# Power3.net
KiCad netlist of a schematic drawn in Altium Designer
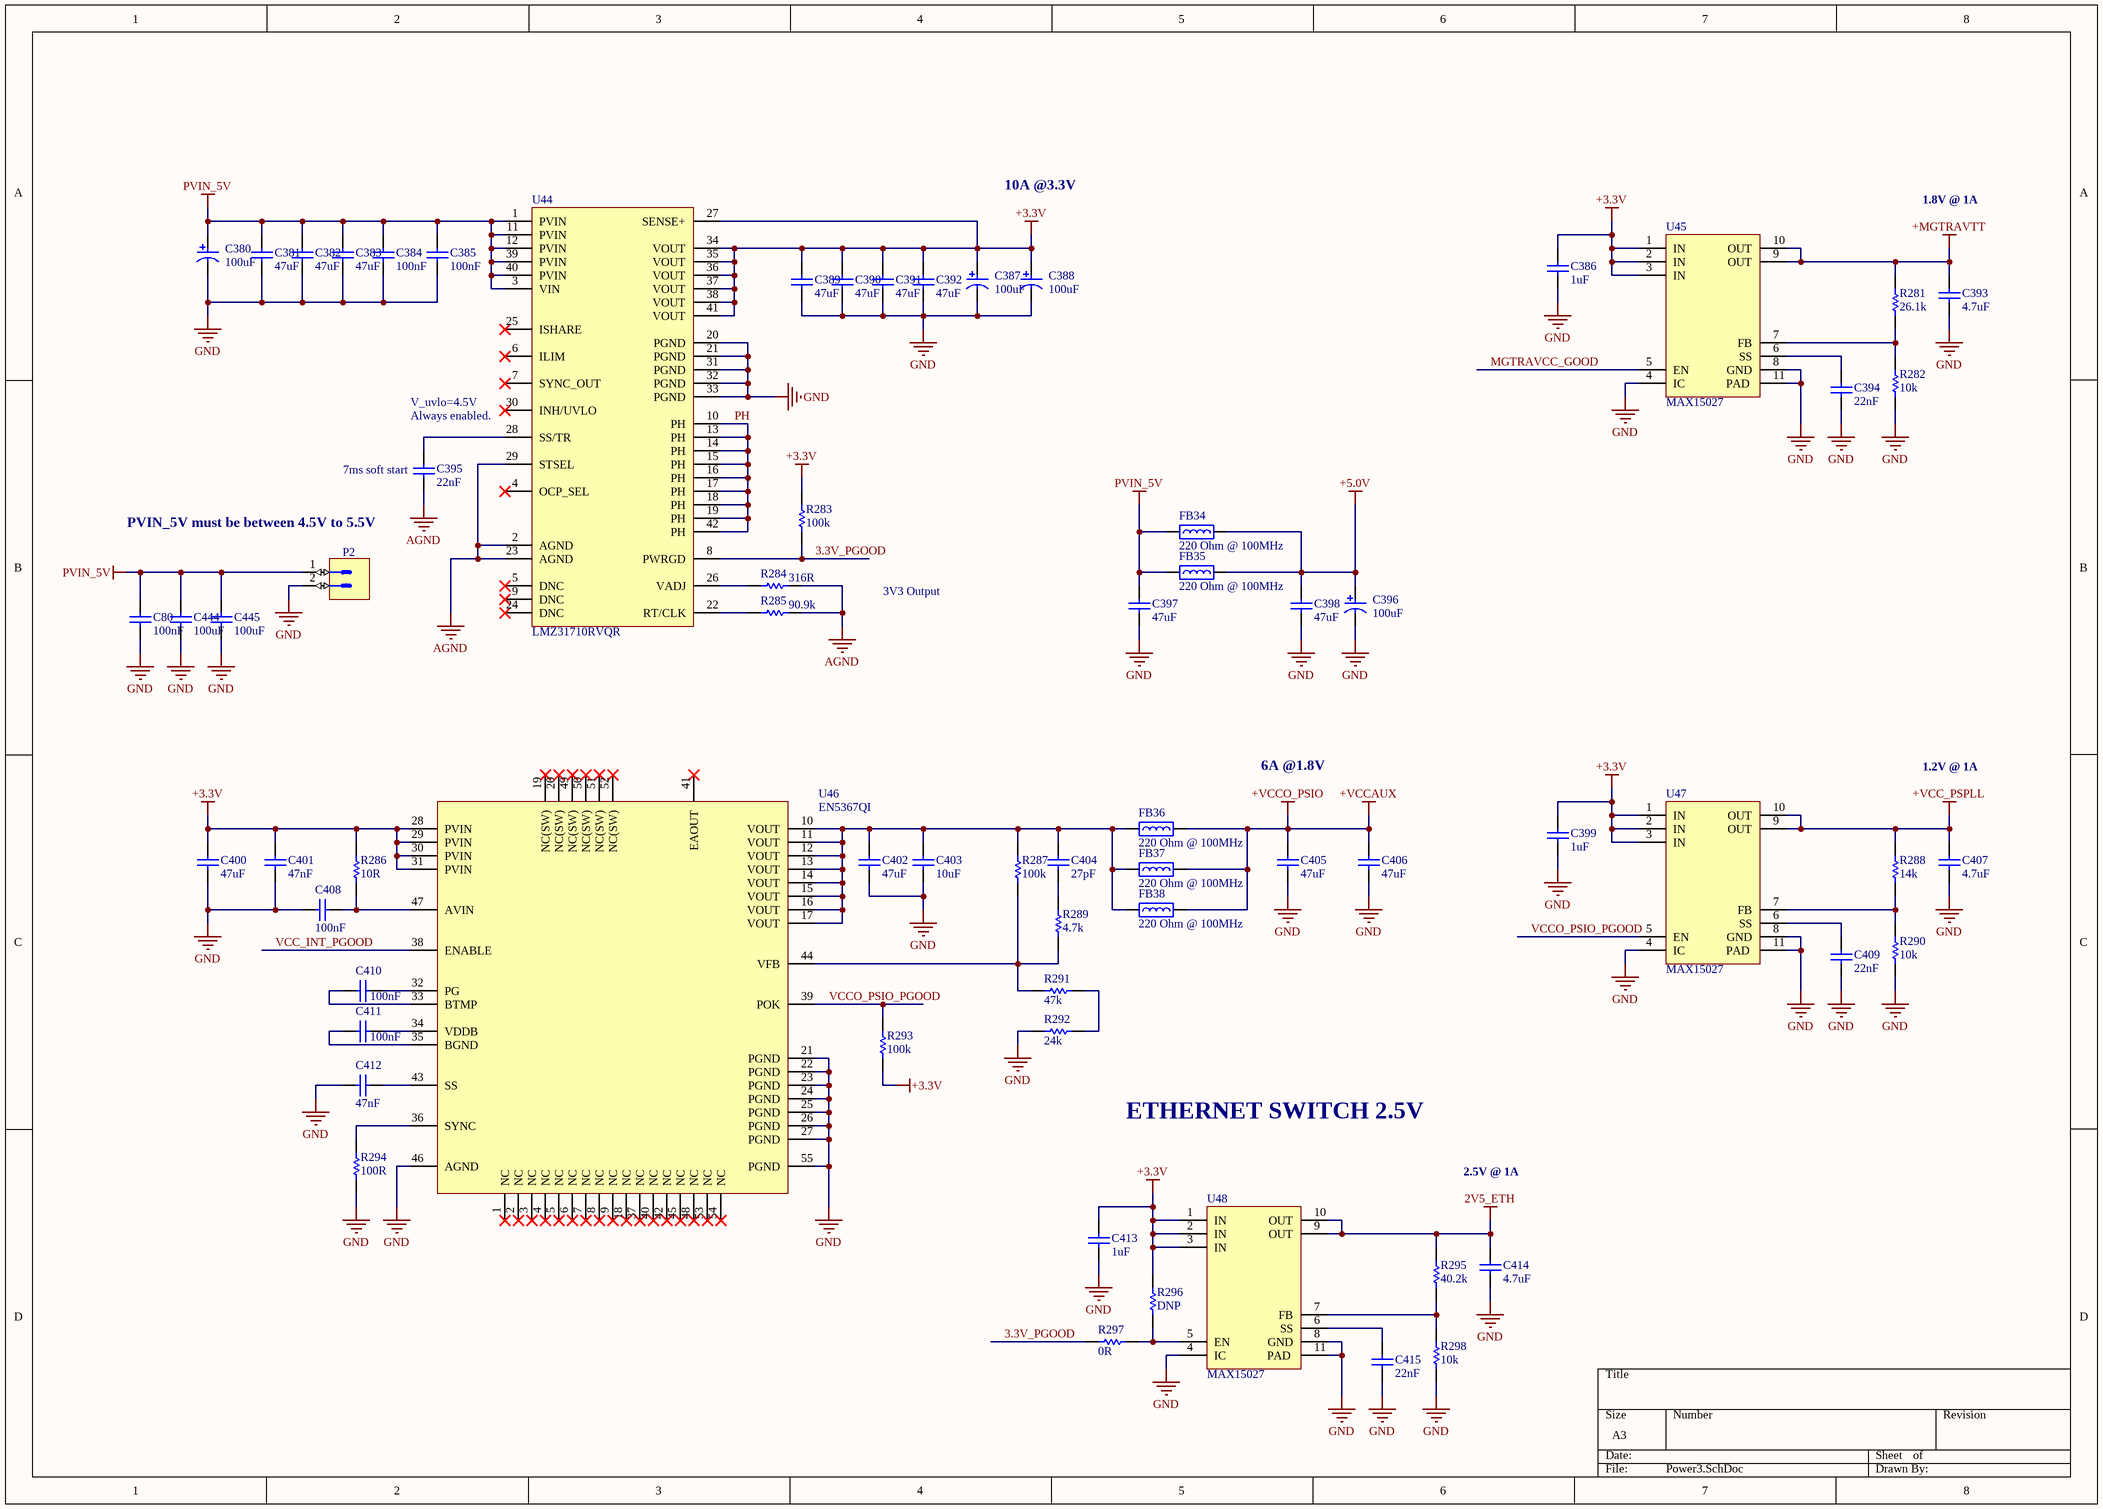
[diagram p0: Power3.SchDoc]

(export (version "E")
  (design (tool "Eeschema 10.0.6"))
  (components
    (comp (ref "C80")
      (value "100nF")
      (footprint "CAPC1005L_0402")
      (description "CAP CER 0.1UF 25V X7R 0402")
      (fields (field (name "VOLTAGE") "25V") (field (name "TOLERANCE") "10%"))
      (libsource (lib "Ultrascale_SchLib") (part "CAPCER0402X7R100N25V_10T"))
    )
    (comp (ref "C380")
      (value "100uF")
      (footprint "AVX_TAN_F95_P_0905")
      (description "CAP TANT 100UF 6.3V 20% 0805")
      (fields (field (name "VOLTAGE") "6.3V") (field (name "TOLERANCE") "20%"))
      (libsource (lib "Ultrascale_SchLib") (part "CAPELE0905TAN100U6V3_20T"))
    )
    (comp (ref "C381")
      (value "47uF")
      (footprint "CAPC3216L_1206")
      (description "CAP CER 47UF 25V X5R 1206")
      (fields (field (name "VOLTAGE") "25V") (field (name "TOLERANCE") "20%"))
      (libsource (lib "Ultrascale_SchLib") (part "CAPCER1206X5R47U25V_20T"))
    )
    (comp (ref "C382")
      (value "47uF")
      (footprint "CAPC3216L_1206")
      (description "CAP CER 47UF 25V X5R 1206")
      (fields (field (name "VOLTAGE") "25V") (field (name "TOLERANCE") "20%"))
      (libsource (lib "Ultrascale_SchLib") (part "CAPCER1206X5R47U25V_20T"))
    )
    (comp (ref "C383")
      (value "47uF")
      (footprint "CAPC3216L_1206")
      (description "CAP CER 47UF 25V X5R 1206")
      (fields (field (name "VOLTAGE") "25V") (field (name "TOLERANCE") "20%"))
      (libsource (lib "Ultrascale_SchLib") (part "CAPCER1206X5R47U25V_20T"))
    )
    (comp (ref "C384")
      (value "100nF")
      (footprint "CAPC1005L_0402")
      (description "CAP CER 0.1UF 25V X7R 0402")
      (fields (field (name "VOLTAGE") "25V") (field (name "TOLERANCE") "10%"))
      (libsource (lib "Ultrascale_SchLib") (part "CAPCER0402X7R100N25V_10T"))
    )
    (comp (ref "C385")
      (value "100nF")
      (footprint "CAPC1005L_0402")
      (description "CAP CER 0.1UF 25V X7R 0402")
      (fields (field (name "VOLTAGE") "25V") (field (name "TOLERANCE") "10%"))
      (libsource (lib "Ultrascale_SchLib") (part "CAPCER0402X7R100N25V_10T"))
    )
    (comp (ref "C386")
      (value "1uF")
      (footprint "CAPC1005L_0402")
      (description "CAP CER 1UF 16V X5R 0402")
      (fields (field (name "VOLTAGE") "16V") (field (name "TOLERANCE") "20%"))
      (libsource (lib "Ultrascale_SchLib") (part "CAPCER0402X5R1U16V_20T"))
    )
    (comp (ref "C387")
      (value "100uF")
      (footprint "AVX_TAN_F95_P_0905")
      (description "CAP TANT 100UF 6.3V 20% 0805")
      (fields (field (name "VOLTAGE") "6.3V") (field (name "TOLERANCE") "20%"))
      (libsource (lib "Ultrascale_SchLib") (part "CAPELE0905TAN100U6V3_20T"))
    )
    (comp (ref "C388")
      (value "100uF")
      (footprint "AVX_TAN_F95_P_0905")
      (description "CAP TANT 100UF 6.3V 20% 0805")
      (fields (field (name "VOLTAGE") "6.3V") (field (name "TOLERANCE") "20%"))
      (libsource (lib "Ultrascale_SchLib") (part "CAPELE0905TAN100U6V3_20T"))
    )
    (comp (ref "C389")
      (value "47uF")
      (footprint "CAPC3216L_1206")
      (description "CAP CER 47UF 25V X5R 1206")
      (fields (field (name "VOLTAGE") "25V") (field (name "TOLERANCE") "20%"))
      (libsource (lib "Ultrascale_SchLib") (part "CAPCER1206X5R47U25V_20T"))
    )
    (comp (ref "C390")
      (value "47uF")
      (footprint "CAPC3216L_1206")
      (description "CAP CER 47UF 25V X5R 1206")
      (fields (field (name "VOLTAGE") "25V") (field (name "TOLERANCE") "20%"))
      (libsource (lib "Ultrascale_SchLib") (part "CAPCER1206X5R47U25V_20T"))
    )
    (comp (ref "C391")
      (value "47uF")
      (footprint "CAPC3216L_1206")
      (description "CAP CER 47UF 25V X5R 1206")
      (fields (field (name "VOLTAGE") "25V") (field (name "TOLERANCE") "20%"))
      (libsource (lib "Ultrascale_SchLib") (part "CAPCER1206X5R47U25V_20T"))
    )
    (comp (ref "C392")
      (value "47uF")
      (footprint "CAPC3216L_1206")
      (description "CAP CER 47UF 25V X5R 1206")
      (fields (field (name "VOLTAGE") "25V") (field (name "TOLERANCE") "20%"))
      (libsource (lib "Ultrascale_SchLib") (part "CAPCER1206X5R47U25V_20T"))
    )
    (comp (ref "C393")
      (value "4.7uF")
      (footprint "CAPC1005L_0402")
      (description "CAP CER 4.7UF 10V X5R 0402")
      (fields (field (name "VOLTAGE") "10V") (field (name "TOLERANCE") "10%"))
      (libsource (lib "Ultrascale_SchLib") (part "CAPCER0402X5R4U710V_10T"))
    )
    (comp (ref "C394")
      (value "22nF")
      (footprint "CAPC1005L_0402")
      (description "CAP CER 0.022UF 50V X7R 0402")
      (fields (field (name "VOLTAGE") "50V") (field (name "TOLERANCE") "10%"))
      (libsource (lib "Ultrascale_SchLib") (part "CAPCER0402X7R22N50V_10T"))
    )
    (comp (ref "C395")
      (value "22nF")
      (footprint "CAPC1005L_0402")
      (description "CAP CER 0.022UF 50V X7R 0402")
      (fields (field (name "VOLTAGE") "50V") (field (name "TOLERANCE") "10%"))
      (libsource (lib "Ultrascale_SchLib") (part "CAPCER0402X7R22N50V_10T"))
    )
    (comp (ref "C396")
      (value "100uF")
      (footprint "AVX_TAN_F95_P_0905")
      (description "CAP TANT 100UF 6.3V 20% 0805")
      (fields (field (name "VOLTAGE") "6.3V") (field (name "TOLERANCE") "20%"))
      (libsource (lib "Ultrascale_SchLib") (part "CAPELE0905TAN100U6V3_20T"))
    )
    (comp (ref "C397")
      (value "47uF")
      (footprint "CAPC3216L_1206")
      (description "CAP CER 47UF 25V X5R 1206")
      (fields (field (name "VOLTAGE") "25V") (field (name "TOLERANCE") "20%"))
      (libsource (lib "Ultrascale_SchLib") (part "CAPCER1206X5R47U25V_20T"))
    )
    (comp (ref "C398")
      (value "47uF")
      (footprint "CAPC3216L_1206")
      (description "CAP CER 47UF 25V X5R 1206")
      (fields (field (name "VOLTAGE") "25V") (field (name "TOLERANCE") "20%"))
      (libsource (lib "Ultrascale_SchLib") (part "CAPCER1206X5R47U25V_20T"))
    )
    (comp (ref "C399")
      (value "1uF")
      (footprint "CAPC1005L_0402")
      (description "CAP CER 1UF 16V X5R 0402")
      (fields (field (name "VOLTAGE") "16V") (field (name "TOLERANCE") "20%"))
      (libsource (lib "Ultrascale_SchLib") (part "CAPCER0402X5R1U16V_20T"))
    )
    (comp (ref "C400")
      (value "47uF")
      (footprint "CAPC3216L_1206")
      (description "CAP CER 47UF 25V X5R 1206")
      (fields (field (name "VOLTAGE") "25V") (field (name "TOLERANCE") "20%"))
      (libsource (lib "Ultrascale_SchLib") (part "CAPCER1206X5R47U25V_20T"))
    )
    (comp (ref "C401")
      (value "47nF")
      (footprint "CAPC2012L_0805")
      (description "CAP CER 0.047UF 50V X7R 0805")
      (fields (field (name "VOLTAGE") "50V") (field (name "TOLERANCE") "10%"))
      (libsource (lib "Ultrascale_SchLib") (part "CAPCER0805X5R47N50V_10T"))
    )
    (comp (ref "C402")
      (value "47uF")
      (footprint "CAPC3216L_1206")
      (description "CAP CER 47UF 25V X5R 1206")
      (fields (field (name "VOLTAGE") "25V") (field (name "TOLERANCE") "20%"))
      (libsource (lib "Ultrascale_SchLib") (part "CAPCER1206X5R47U25V_20T"))
    )
    (comp (ref "C403")
      (value "10uF")
      (footprint "CAPC1005L_0402")
      (description "CAP CER 10UF 10V X5R 0402")
      (fields (field (name "VOLTAGE") "10V") (field (name "TOLERANCE") "20%"))
      (libsource (lib "Ultrascale_SchLib") (part "CAPCER0402X5R10U10V_20T"))
    )
    (comp (ref "C404")
      (value "27pF")
      (footprint "CAPC1005L_0402")
      (description "CAP CER 27PF 50V C0G/NP0 0402")
      (fields (field (name "VOLTAGE") "50V") (field (name "TOLERANCE") "5%"))
      (libsource (lib "Ultrascale_SchLib") (part "CAPCER0402C0G27P50V_5T"))
    )
    (comp (ref "C405")
      (value "47uF")
      (footprint "CAPC3216L_1206")
      (description "CAP CER 47UF 25V X5R 1206")
      (fields (field (name "VOLTAGE") "25V") (field (name "TOLERANCE") "20%"))
      (libsource (lib "Ultrascale_SchLib") (part "CAPCER1206X5R47U25V_20T"))
    )
    (comp (ref "C406")
      (value "47uF")
      (footprint "CAPC3216L_1206")
      (description "CAP CER 47UF 25V X5R 1206")
      (fields (field (name "VOLTAGE") "25V") (field (name "TOLERANCE") "20%"))
      (libsource (lib "Ultrascale_SchLib") (part "CAPCER1206X5R47U25V_20T"))
    )
    (comp (ref "C407")
      (value "4.7uF")
      (footprint "CAPC1005L_0402")
      (description "CAP CER 4.7UF 10V X5R 0402")
      (fields (field (name "VOLTAGE") "10V") (field (name "TOLERANCE") "10%"))
      (libsource (lib "Ultrascale_SchLib") (part "CAPCER0402X5R4U710V_10T"))
    )
    (comp (ref "C408")
      (value "100nF")
      (footprint "CAPC1005L_0402")
      (description "CAP CER 0.1UF 25V X7R 0402")
      (fields (field (name "VOLTAGE") "25V") (field (name "TOLERANCE") "10%"))
      (libsource (lib "Ultrascale_SchLib") (part "CAPCER0402X7R100N25V_10T"))
    )
    (comp (ref "C409")
      (value "22nF")
      (footprint "CAPC1005L_0402")
      (description "CAP CER 0.022UF 50V X7R 0402")
      (fields (field (name "VOLTAGE") "50V") (field (name "TOLERANCE") "10%"))
      (libsource (lib "Ultrascale_SchLib") (part "CAPCER0402X7R22N50V_10T"))
    )
    (comp (ref "C410")
      (value "100nF")
      (footprint "CAPC1005L_0402")
      (description "CAP CER 0.1UF 25V X7R 0402")
      (fields (field (name "VOLTAGE") "25V") (field (name "TOLERANCE") "10%"))
      (libsource (lib "Ultrascale_SchLib") (part "CAPCER0402X7R100N25V_10T"))
    )
    (comp (ref "C411")
      (value "100nF")
      (footprint "CAPC1005L_0402")
      (description "CAP CER 0.1UF 25V X7R 0402")
      (fields (field (name "VOLTAGE") "25V") (field (name "TOLERANCE") "10%"))
      (libsource (lib "Ultrascale_SchLib") (part "CAPCER0402X7R100N25V_10T"))
    )
    (comp (ref "C412")
      (value "47nF")
      (footprint "CAPC2012L_0805")
      (description "CAP CER 0.047UF 50V X7R 0805")
      (fields (field (name "VOLTAGE") "50V") (field (name "TOLERANCE") "10%"))
      (libsource (lib "Ultrascale_SchLib") (part "CAPCER0805X5R47N50V_10T"))
    )
    (comp (ref "C413")
      (value "1uF")
      (footprint "CAPC1005L_0402")
      (description "CAP CER 1UF 16V X5R 0402")
      (fields (field (name "VOLTAGE") "16V") (field (name "TOLERANCE") "20%"))
      (libsource (lib "Ultrascale_SchLib") (part "CAPCER0402X5R1U16V_20T"))
    )
    (comp (ref "C414")
      (value "4.7uF")
      (footprint "CAPC1005L_0402")
      (description "CAP CER 4.7UF 10V X5R 0402")
      (fields (field (name "VOLTAGE") "10V") (field (name "TOLERANCE") "10%"))
      (libsource (lib "Ultrascale_SchLib") (part "CAPCER0402X5R4U710V_10T"))
    )
    (comp (ref "C415")
      (value "22nF")
      (footprint "CAPC1005L_0402")
      (description "CAP CER 0.022UF 50V X7R 0402")
      (fields (field (name "VOLTAGE") "50V") (field (name "TOLERANCE") "10%"))
      (libsource (lib "Ultrascale_SchLib") (part "CAPCER0402X7R22N50V_10T"))
    )
    (comp (ref "C444")
      (value "100uF")
      (footprint "CAPC3225N_1210")
      (description "CAP CER 100UF 16V X5R 1210")
      (fields (field (name "VOLTAGE") "16V") (field (name "TOLERANCE") "20%"))
      (libsource (lib "Ultrascale_SchLib") (part "CAPCER1210X5R100U16V_20T"))
    )
    (comp (ref "C445")
      (value "100uF")
      (footprint "CAPC3225N_1210")
      (description "CAP CER 100UF 16V X5R 1210")
      (fields (field (name "VOLTAGE") "16V") (field (name "TOLERANCE") "20%"))
      (libsource (lib "Ultrascale_SchLib") (part "CAPCER1210X5R100U16V_20T"))
    )
    (comp (ref "FB34")
      (value "BEAD0603_220_2A5_40M")
      (footprint "INDC1608N_0603")
      (description "FERRITE BEAD 220 OHM 0603 1LN")
      (fields (field (name "IMPEDANCE @ FREQUENCY") "220 Ohm @ 100MHz"))
      (libsource (lib "Ultrascale_SchLib") (part "BEAD0603_220_2A5_40M"))
    )
    (comp (ref "FB35")
      (value "BEAD0603_220_2A5_40M")
      (footprint "INDC1608N_0603")
      (description "FERRITE BEAD 220 OHM 0603 1LN")
      (fields (field (name "IMPEDANCE @ FREQUENCY") "220 Ohm @ 100MHz"))
      (libsource (lib "Ultrascale_SchLib") (part "BEAD0603_220_2A5_40M"))
    )
    (comp (ref "FB36")
      (value "BEAD0603_220_2A5_40M")
      (footprint "INDC1608N_0603")
      (description "FERRITE BEAD 220 OHM 0603 1LN")
      (fields (field (name "IMPEDANCE @ FREQUENCY") "220 Ohm @ 100MHz"))
      (libsource (lib "Ultrascale_SchLib") (part "BEAD0603_220_2A5_40M"))
    )
    (comp (ref "FB37")
      (value "BEAD0603_220_2A5_40M")
      (footprint "INDC1608N_0603")
      (description "FERRITE BEAD 220 OHM 0603 1LN")
      (fields (field (name "IMPEDANCE @ FREQUENCY") "220 Ohm @ 100MHz"))
      (libsource (lib "Ultrascale_SchLib") (part "BEAD0603_220_2A5_40M"))
    )
    (comp (ref "FB38")
      (value "BEAD0603_220_2A5_40M")
      (footprint "INDC1608N_0603")
      (description "FERRITE BEAD 220 OHM 0603 1LN")
      (fields (field (name "IMPEDANCE @ FREQUENCY") "220 Ohm @ 100MHz"))
      (libsource (lib "Ultrascale_SchLib") (part "BEAD0603_220_2A5_40M"))
    )
    (comp (ref "P2")
      (value "KK®")
      (footprint "MOLEX_26-60-4020")
      (description "Connector 2 Male")
      (fields
        (field (name "PART NUMBER") "MOLEX_26-60-4020")
        (field (name "MANUFACTURER") "Molex, LLC")
        (field (name "AUTHOR") "CERN DEM JLC")
      )
      (libsource (lib "Ultrascale_SchLib") (part "MOLEX_26-60-4020"))
    )
    (comp (ref "R281")
      (value "26.1k")
      (footprint "RESC1005L_0402")
      (description "RES SMD 26.1K OHM 1% 1/10W 0402")
      (fields (field (name "POWER") "1/10W") (field (name "TOLERANCE") "1%"))
      (libsource (lib "Ultrascale_SchLib") (part "RES0402_26K1_0W1_1T"))
    )
    (comp (ref "R282")
      (value "10k")
      (footprint "RESC1005L_0402")
      (description "RES SMD 10K OHM 0.5% 1/16W 0402")
      (fields (field (name "POWER") "1/16W") (field (name "TOLERANCE") "0.5%"))
      (libsource (lib "Ultrascale_SchLib") (part "RES0402_10K_0W1_05T"))
    )
    (comp (ref "R283")
      (value "100k")
      (footprint "RESC1005L_0402")
      (description "RES SMD 100K OHM 1% 1/5W 0402")
      (fields (field (name "POWER") "1/5W") (field (name "TOLERANCE") "1%"))
      (libsource (lib "Ultrascale_SchLib") (part "RES0402_100K_0W2_1T"))
    )
    (comp (ref "R284")
      (value "316R")
      (footprint "RESC1005L_0402")
      (description "RES SMD 316 OHM 1% 1/16W 0402")
      (fields (field (name "POWER") "1/16W") (field (name "TOLERANCE") "1%"))
      (libsource (lib "Ultrascale_SchLib") (part "RES0402_316R_0W06_1T"))
    )
    (comp (ref "R285")
      (value "90.9k")
      (footprint "RESC1005L_0402")
      (description "RES SMD 90.9K OHM 1% 1/10W 0402")
      (fields (field (name "POWER") "1/10W") (field (name "TOLERANCE") "1%"))
      (libsource (lib "Ultrascale_SchLib") (part "RES0402_90K9_0W1_1T"))
    )
    (comp (ref "R286")
      (value "10R")
      (footprint "RESC1005L_0402")
      (description "RES SMD 10 OHM 1% 1/10W 0402")
      (fields (field (name "POWER") "1/10W") (field (name "TOLERANCE") "1%"))
      (libsource (lib "Ultrascale_SchLib") (part "RES0402_10R_0W1_1T"))
    )
    (comp (ref "R287")
      (value "100k")
      (footprint "RESC1005L_0402")
      (description "RES SMD 100K OHM 1% 1/5W 0402")
      (fields (field (name "POWER") "1/5W") (field (name "TOLERANCE") "1%"))
      (libsource (lib "Ultrascale_SchLib") (part "RES0402_100K_0W2_1T"))
    )
    (comp (ref "R288")
      (value "14k")
      (footprint "RESC1005L_0402")
      (description "RES SMD 14K OHM 1% 1/10W 0402")
      (fields (field (name "POWER") "1/10W") (field (name "TOLERANCE") "1%"))
      (libsource (lib "Ultrascale_SchLib") (part "RES0402_14K_0W1_1T"))
    )
    (comp (ref "R289")
      (value "4.7k")
      (footprint "RESC1005L_0402")
      (description "RES SMD 4.7K OHM 1% 1/10W 0402")
      (fields (field (name "POWER") "1/10W") (field (name "TOLERANCE") "1%"))
      (libsource (lib "Ultrascale_SchLib") (part "RES0402_4K7_0W1_1T"))
    )
    (comp (ref "R290")
      (value "10k")
      (footprint "RESC1005L_0402")
      (description "RES SMD 10K OHM 0.5% 1/16W 0402")
      (fields (field (name "POWER") "1/16W") (field (name "TOLERANCE") "0.5%"))
      (libsource (lib "Ultrascale_SchLib") (part "RES0402_10K_0W1_05T"))
    )
    (comp (ref "R291")
      (value "47k")
      (footprint "RESC1005L_0402")
      (description "RES SMD 47K OHM 1% 1/10W 0402")
      (fields (field (name "POWER") "1/10W") (field (name "TOLERANCE") "1%"))
      (libsource (lib "Ultrascale_SchLib") (part "RES0402_47K_0W1"))
    )
    (comp (ref "R292")
      (value "24k")
      (footprint "RESC1005L_0402")
      (description "RES SMD 24K OHM 1% 1/10W 0402")
      (fields (field (name "POWER") "1/10W") (field (name "TOLERANCE") "1%"))
      (libsource (lib "Ultrascale_SchLib") (part "RES0402_24K_0W1"))
    )
    (comp (ref "R293")
      (value "100k")
      (footprint "RESC1005L_0402")
      (description "RES SMD 100K OHM 1% 1/5W 0402")
      (fields (field (name "POWER") "1/5W") (field (name "TOLERANCE") "1%"))
      (libsource (lib "Ultrascale_SchLib") (part "RES0402_100K_0W2_1T"))
    )
    (comp (ref "R294")
      (value "100R")
      (footprint "RESC1005L_0402")
      (description "RES SMD 100 OHM 1% 1/10W 0402")
      (fields (field (name "POWER") "1/10W") (field (name "TOLERANCE") "1%"))
      (libsource (lib "Ultrascale_SchLib") (part "RES0402_100R_0W1_1T"))
    )
    (comp (ref "R295")
      (value "40.2k")
      (footprint "RESC1005L_0402")
      (description "RES SMD 40.2K OHM 1% 1/10W 0402")
      (fields (field (name "POWER") "1/10W") (field (name "TOLERANCE") "1%"))
      (libsource (lib "Ultrascale_SchLib") (part "RES0402_40K2_0W1_1T"))
    )
    (comp (ref "R296")
      (value "DNP")
      (footprint "RESC1005L_0402")
      (description "RES SMD 0402 Footprint")
      (fields (field (name "Comment") "RES0402"))
      (libsource (lib "Ultrascale_SchLib") (part "RES0402"))
    )
    (comp (ref "R297")
      (value "0R")
      (footprint "RESC1005L_0402")
      (description "RES SMD 0 OHM JUMPER 1/16W 0402")
      (fields (field (name "POWER") "0.063W, 1/16W") (field (name "Comment") "RES0402_0R"))
      (libsource (lib "Ultrascale_SchLib") (part "RES0402_0R"))
    )
    (comp (ref "R298")
      (value "10k")
      (footprint "RESC1005L_0402")
      (description "RES SMD 10K OHM 0.5% 1/16W 0402")
      (fields (field (name "POWER") "1/16W") (field (name "TOLERANCE") "0.5%"))
      (libsource (lib "Ultrascale_SchLib") (part "RES0402_10K_0W1_05T"))
    )
    (comp (ref "U44")
      (value "LMZ31710RVQR")
      (footprint "LMZ31710RVQR")
      (description "DC/DC CONVERTER 0.6-5.5V 55W")
      (libsource (lib "Ultrascale_SchLib") (part "LMZ31710RVQR"))
    )
    (comp (ref "U45")
      (value "MAX15027")
      (footprint "MAX15027_T1033+1_V")
      (description "IC REG LINEAR POS ADJ 1A 10TDFN")
      (libsource (lib "Ultrascale_SchLib") (part "MAX15027"))
    )
    (comp (ref "U46")
      (value "EN5367QI")
      (footprint "QFN54-EN5367QI")
      (description "DC/DC CONVERTER 0.6-4.9V 29W")
      (libsource (lib "Ultrascale_SchLib") (part "EN5367QI"))
    )
    (comp (ref "U47")
      (value "MAX15027")
      (footprint "MAX15027_T1033+1_V")
      (description "IC REG LINEAR POS ADJ 1A 10TDFN")
      (libsource (lib "Ultrascale_SchLib") (part "MAX15027"))
    )
    (comp (ref "U48")
      (value "MAX15027")
      (footprint "MAX15027_T1033+1_V")
      (description "IC REG LINEAR POS ADJ 1A 10TDFN")
      (libsource (lib "Ultrascale_SchLib") (part "MAX15027"))
    )
  )
  (nets
    (net (code "1") (name "+3.3V") (class "Default")
      (node (ref "C386") (pin "2") (pinfunction "2_2") (pintype "passive"))
      (node (ref "C387") (pin "1") (pinfunction "1_1") (pintype "passive"))
      (node (ref "C388") (pin "1") (pinfunction "1_1") (pintype "passive"))
      (node (ref "C389") (pin "2") (pinfunction "2_2") (pintype "passive"))
      (node (ref "C390") (pin "2") (pinfunction "2_2") (pintype "passive"))
      (node (ref "C391") (pin "2") (pinfunction "2_2") (pintype "passive"))
      (node (ref "C392") (pin "2") (pinfunction "2_2") (pintype "passive"))
      (node (ref "C399") (pin "2") (pinfunction "2_2") (pintype "passive"))
      (node (ref "C400") (pin "2") (pinfunction "2_2") (pintype "passive"))
      (node (ref "C401") (pin "2") (pinfunction "2_2") (pintype "passive"))
      (node (ref "C413") (pin "2") (pinfunction "2_2") (pintype "passive"))
      (node (ref "R283") (pin "2") (pinfunction "2_2") (pintype "passive"))
      (node (ref "R286") (pin "2") (pinfunction "2_2") (pintype "passive"))
      (node (ref "R293") (pin "2") (pinfunction "2_2") (pintype "passive"))
      (node (ref "R296") (pin "2") (pinfunction "2_2") (pintype "passive"))
      (node (ref "U44") (pin "27") (pinfunction "SENSE+_27") (pintype "power_in"))
      (node (ref "U44") (pin "34") (pinfunction "VOUT_34") (pintype "power_in"))
      (node (ref "U44") (pin "35") (pinfunction "VOUT_35") (pintype "power_in"))
      (node (ref "U44") (pin "36") (pinfunction "VOUT_36") (pintype "power_in"))
      (node (ref "U44") (pin "37") (pinfunction "VOUT_37") (pintype "power_in"))
      (node (ref "U44") (pin "38") (pinfunction "VOUT_38") (pintype "power_in"))
      (node (ref "U44") (pin "41") (pinfunction "VOUT_41") (pintype "power_in"))
      (node (ref "U45") (pin "1") (pinfunction "IN_1") (pintype "passive"))
      (node (ref "U45") (pin "2") (pinfunction "IN_2") (pintype "passive"))
      (node (ref "U45") (pin "3") (pinfunction "IN_3") (pintype "passive"))
      (node (ref "U46") (pin "28") (pinfunction "PVIN_28") (pintype "power_in"))
      (node (ref "U46") (pin "29") (pinfunction "PVIN_29") (pintype "power_in"))
      (node (ref "U46") (pin "30") (pinfunction "PVIN_30") (pintype "power_in"))
      (node (ref "U46") (pin "31") (pinfunction "PVIN_31") (pintype "power_in"))
      (node (ref "U47") (pin "1") (pinfunction "IN_1") (pintype "passive"))
      (node (ref "U47") (pin "2") (pinfunction "IN_2") (pintype "passive"))
      (node (ref "U47") (pin "3") (pinfunction "IN_3") (pintype "passive"))
      (node (ref "U48") (pin "1") (pinfunction "IN_1") (pintype "passive"))
      (node (ref "U48") (pin "2") (pinfunction "IN_2") (pintype "passive"))
      (node (ref "U48") (pin "3") (pinfunction "IN_3") (pintype "passive"))
    )
    (net (code "2") (name "+5.0V") (class "Default")
      (node (ref "C396") (pin "1") (pinfunction "1_1") (pintype "passive"))
      (node (ref "C398") (pin "2") (pinfunction "2_2") (pintype "passive"))
      (node (ref "FB34") (pin "2") (pinfunction "2_2") (pintype "passive"))
      (node (ref "FB35") (pin "2") (pinfunction "2_2") (pintype "passive"))
    )
    (net (code "3") (name "+MGTRAVTT") (class "Default")
      (node (ref "C393") (pin "2") (pinfunction "2_2") (pintype "passive"))
      (node (ref "R281") (pin "2") (pinfunction "2_2") (pintype "passive"))
      (node (ref "U45") (pin "10") (pinfunction "OUT_10") (pintype "passive"))
      (node (ref "U45") (pin "9") (pinfunction "OUT_9") (pintype "passive"))
    )
    (net (code "4") (name "+VCCAUX") (class "Default")
      (node (ref "C405") (pin "2") (pinfunction "2_2") (pintype "passive"))
      (node (ref "C406") (pin "2") (pinfunction "2_2") (pintype "passive"))
      (node (ref "FB36") (pin "2") (pinfunction "2_2") (pintype "passive"))
      (node (ref "FB37") (pin "2") (pinfunction "2_2") (pintype "passive"))
      (node (ref "FB38") (pin "2") (pinfunction "2_2") (pintype "passive"))
    )
    (net (code "5") (name "+VCC_PSPLL") (class "Default")
      (node (ref "C407") (pin "2") (pinfunction "2_2") (pintype "passive"))
      (node (ref "R288") (pin "2") (pinfunction "2_2") (pintype "passive"))
      (node (ref "U47") (pin "10") (pinfunction "OUT_10") (pintype "passive"))
      (node (ref "U47") (pin "9") (pinfunction "OUT_9") (pintype "passive"))
    )
    (net (code "6") (name "/3.3V_PGOOD") (class "Default")
      (node (ref "R283") (pin "1") (pinfunction "1_1") (pintype "passive"))
      (node (ref "R297") (pin "1") (pinfunction "1_1") (pintype "passive"))
      (node (ref "U44") (pin "8") (pinfunction "PWRGD_8") (pintype "power_in"))
    )
    (net (code "7") (name "/MGTRAVCC_GOOD") (class "Default")
      (node (ref "U45") (pin "5") (pinfunction "EN_5") (pintype "passive"))
    )
    (net (code "8") (name "/PH") (class "Default")
      (node (ref "U44") (pin "10") (pinfunction "PH_10") (pintype "power_in"))
      (node (ref "U44") (pin "13") (pinfunction "PH_13") (pintype "power_in"))
      (node (ref "U44") (pin "14") (pinfunction "PH_14") (pintype "power_in"))
      (node (ref "U44") (pin "15") (pinfunction "PH_15") (pintype "power_in"))
      (node (ref "U44") (pin "16") (pinfunction "PH_16") (pintype "power_in"))
      (node (ref "U44") (pin "17") (pinfunction "PH_17") (pintype "power_in"))
      (node (ref "U44") (pin "18") (pinfunction "PH_18") (pintype "power_in"))
      (node (ref "U44") (pin "19") (pinfunction "PH_19") (pintype "power_in"))
      (node (ref "U44") (pin "42") (pinfunction "PH_42") (pintype "power_in"))
    )
    (net (code "9") (name "/VCCO_PSIO_PGOOD") (class "Default")
      (node (ref "R293") (pin "1") (pinfunction "1_1") (pintype "passive"))
      (node (ref "U46") (pin "39") (pinfunction "POK_39") (pintype "power_in"))
      (node (ref "U47") (pin "5") (pinfunction "EN_5") (pintype "passive"))
    )
    (net (code "10") (name "/VCC_INT_PGOOD") (class "Default")
      (node (ref "U46") (pin "38") (pinfunction "ENABLE_38") (pintype "power_in"))
    )
    (net (code "11") (name "2V5_ETH") (class "Default")
      (node (ref "C414") (pin "2") (pinfunction "2_2") (pintype "passive"))
      (node (ref "R295") (pin "2") (pinfunction "2_2") (pintype "passive"))
      (node (ref "U48") (pin "10") (pinfunction "OUT_10") (pintype "passive"))
      (node (ref "U48") (pin "9") (pinfunction "OUT_9") (pintype "passive"))
    )
    (net (code "12") (name "AGND") (class "Default")
      (node (ref "C395") (pin "1") (pinfunction "1_1") (pintype "passive"))
      (node (ref "R284") (pin "2") (pinfunction "2_2") (pintype "passive"))
      (node (ref "R285") (pin "2") (pinfunction "2_2") (pintype "passive"))
      (node (ref "U44") (pin "2") (pinfunction "AGND_2") (pintype "power_in"))
      (node (ref "U44") (pin "23") (pinfunction "AGND_23") (pintype "power_in"))
      (node (ref "U44") (pin "29") (pinfunction "STSEL_29") (pintype "power_in"))
    )
    (net (code "13") (name "GND") (class "Default")
      (node (ref "C380") (pin "2") (pinfunction "2_2") (pintype "passive"))
      (node (ref "C381") (pin "1") (pinfunction "1_1") (pintype "passive"))
      (node (ref "C382") (pin "1") (pinfunction "1_1") (pintype "passive"))
      (node (ref "C383") (pin "1") (pinfunction "1_1") (pintype "passive"))
      (node (ref "C384") (pin "2") (pinfunction "2_2") (pintype "passive"))
      (node (ref "C385") (pin "2") (pinfunction "2_2") (pintype "passive"))
      (node (ref "C386") (pin "1") (pinfunction "1_1") (pintype "passive"))
      (node (ref "C387") (pin "2") (pinfunction "2_2") (pintype "passive"))
      (node (ref "C388") (pin "2") (pinfunction "2_2") (pintype "passive"))
      (node (ref "C389") (pin "1") (pinfunction "1_1") (pintype "passive"))
      (node (ref "C390") (pin "1") (pinfunction "1_1") (pintype "passive"))
      (node (ref "C391") (pin "1") (pinfunction "1_1") (pintype "passive"))
      (node (ref "C392") (pin "1") (pinfunction "1_1") (pintype "passive"))
      (node (ref "C393") (pin "1") (pinfunction "1_1") (pintype "passive"))
      (node (ref "C394") (pin "1") (pinfunction "1_1") (pintype "passive"))
      (node (ref "C396") (pin "2") (pinfunction "2_2") (pintype "passive"))
      (node (ref "C397") (pin "1") (pinfunction "1_1") (pintype "passive"))
      (node (ref "C398") (pin "1") (pinfunction "1_1") (pintype "passive"))
      (node (ref "C399") (pin "1") (pinfunction "1_1") (pintype "passive"))
      (node (ref "C400") (pin "1") (pinfunction "1_1") (pintype "passive"))
      (node (ref "C401") (pin "1") (pinfunction "1_1") (pintype "passive"))
      (node (ref "C402") (pin "1") (pinfunction "1_1") (pintype "passive"))
      (node (ref "C403") (pin "1") (pinfunction "1_1") (pintype "passive"))
      (node (ref "C405") (pin "1") (pinfunction "1_1") (pintype "passive"))
      (node (ref "C406") (pin "1") (pinfunction "1_1") (pintype "passive"))
      (node (ref "C407") (pin "1") (pinfunction "1_1") (pintype "passive"))
      (node (ref "C408") (pin "2") (pinfunction "2_2") (pintype "passive"))
      (node (ref "C409") (pin "1") (pinfunction "1_1") (pintype "passive"))
      (node (ref "C412") (pin "2") (pinfunction "2_2") (pintype "passive"))
      (node (ref "C413") (pin "1") (pinfunction "1_1") (pintype "passive"))
      (node (ref "C414") (pin "1") (pinfunction "1_1") (pintype "passive"))
      (node (ref "C415") (pin "1") (pinfunction "1_1") (pintype "passive"))
      (node (ref "C444") (pin "1") (pinfunction "1_1") (pintype "passive"))
      (node (ref "C445") (pin "1") (pinfunction "1_1") (pintype "passive"))
      (node (ref "C80") (pin "2") (pinfunction "2_2") (pintype "passive"))
      (node (ref "P2") (pin "2") (pinfunction "2_2") (pintype "bidirectional"))
      (node (ref "R282") (pin "1") (pinfunction "1_1") (pintype "passive"))
      (node (ref "R290") (pin "1") (pinfunction "1_1") (pintype "passive"))
      (node (ref "R292") (pin "1") (pinfunction "1_1") (pintype "passive"))
      (node (ref "R294") (pin "2") (pinfunction "2_2") (pintype "passive"))
      (node (ref "R298") (pin "1") (pinfunction "1_1") (pintype "passive"))
      (node (ref "U44") (pin "20") (pinfunction "PGND_20") (pintype "power_in"))
      (node (ref "U44") (pin "21") (pinfunction "PGND_21") (pintype "power_in"))
      (node (ref "U44") (pin "31") (pinfunction "PGND_31") (pintype "power_in"))
      (node (ref "U44") (pin "32") (pinfunction "PGND_32") (pintype "power_in"))
      (node (ref "U44") (pin "33") (pinfunction "PGND_33") (pintype "power_in"))
      (node (ref "U45") (pin "11") (pinfunction "PAD_11") (pintype "passive"))
      (node (ref "U45") (pin "4") (pinfunction "IC_4") (pintype "passive"))
      (node (ref "U45") (pin "8") (pinfunction "GND_8") (pintype "passive"))
      (node (ref "U46") (pin "21") (pinfunction "PGND_21") (pintype "power_in"))
      (node (ref "U46") (pin "22") (pinfunction "PGND_22") (pintype "power_in"))
      (node (ref "U46") (pin "23") (pinfunction "PGND_23") (pintype "power_in"))
      (node (ref "U46") (pin "24") (pinfunction "PGND_24") (pintype "power_in"))
      (node (ref "U46") (pin "25") (pinfunction "PGND_25") (pintype "power_in"))
      (node (ref "U46") (pin "26") (pinfunction "PGND_26") (pintype "power_in"))
      (node (ref "U46") (pin "27") (pinfunction "PGND_27") (pintype "power_in"))
      (node (ref "U46") (pin "46") (pinfunction "AGND_46") (pintype "power_in"))
      (node (ref "U46") (pin "55") (pinfunction "PGND_55") (pintype "power_in"))
      (node (ref "U47") (pin "11") (pinfunction "PAD_11") (pintype "passive"))
      (node (ref "U47") (pin "4") (pinfunction "IC_4") (pintype "passive"))
      (node (ref "U47") (pin "8") (pinfunction "GND_8") (pintype "passive"))
      (node (ref "U48") (pin "11") (pinfunction "PAD_11") (pintype "passive"))
      (node (ref "U48") (pin "4") (pinfunction "IC_4") (pintype "passive"))
      (node (ref "U48") (pin "8") (pinfunction "GND_8") (pintype "passive"))
    )
    (net (code "14") (name "Net-(C402-Pad2)") (class "Default")
      (node (ref "C402") (pin "2") (pinfunction "2_2") (pintype "passive"))
      (node (ref "C403") (pin "2") (pinfunction "2_2") (pintype "passive"))
      (node (ref "C404") (pin "2") (pinfunction "2_2") (pintype "passive"))
      (node (ref "FB36") (pin "1") (pinfunction "1_1") (pintype "passive"))
      (node (ref "FB37") (pin "1") (pinfunction "1_1") (pintype "passive"))
      (node (ref "FB38") (pin "1") (pinfunction "1_1") (pintype "passive"))
      (node (ref "R287") (pin "2") (pinfunction "2_2") (pintype "passive"))
      (node (ref "U46") (pin "10") (pinfunction "VOUT_10") (pintype "power_in"))
      (node (ref "U46") (pin "11") (pinfunction "VOUT_11") (pintype "power_in"))
      (node (ref "U46") (pin "12") (pinfunction "VOUT_12") (pintype "power_in"))
      (node (ref "U46") (pin "13") (pinfunction "VOUT_13") (pintype "power_in"))
      (node (ref "U46") (pin "14") (pinfunction "VOUT_14") (pintype "power_in"))
      (node (ref "U46") (pin "15") (pinfunction "VOUT_15") (pintype "power_in"))
      (node (ref "U46") (pin "16") (pinfunction "VOUT_16") (pintype "power_in"))
      (node (ref "U46") (pin "17") (pinfunction "VOUT_17") (pintype "power_in"))
    )
    (net (code "15") (name "Net-(C404-Pad1)") (class "Default")
      (node (ref "C404") (pin "1") (pinfunction "1_1") (pintype "passive"))
      (node (ref "R289") (pin "2") (pinfunction "2_2") (pintype "passive"))
    )
    (net (code "16") (name "Net-(R291-Pad1)") (class "Default")
      (node (ref "R291") (pin "1") (pinfunction "1_1") (pintype "passive"))
      (node (ref "R292") (pin "2") (pinfunction "2_2") (pintype "passive"))
    )
    (net (code "17") (name "Net-(U44-RT{slash}CLK)") (class "Default")
      (node (ref "R285") (pin "1") (pinfunction "1_1") (pintype "passive"))
      (node (ref "U44") (pin "22") (pinfunction "RT/CLK_22") (pintype "power_in"))
    )
    (net (code "18") (name "Net-(U44-SS{slash}TR)") (class "Default")
      (node (ref "C395") (pin "2") (pinfunction "2_2") (pintype "passive"))
      (node (ref "U44") (pin "28") (pinfunction "SS/TR_28") (pintype "power_in"))
    )
    (net (code "19") (name "Net-(U44-VADJ)") (class "Default")
      (node (ref "R284") (pin "1") (pinfunction "1_1") (pintype "passive"))
      (node (ref "U44") (pin "26") (pinfunction "VADJ_26") (pintype "power_in"))
    )
    (net (code "20") (name "Net-(U45-FB)") (class "Default")
      (node (ref "R281") (pin "1") (pinfunction "1_1") (pintype "passive"))
      (node (ref "R282") (pin "2") (pinfunction "2_2") (pintype "passive"))
      (node (ref "U45") (pin "7") (pinfunction "FB_7") (pintype "passive"))
    )
    (net (code "21") (name "Net-(U45-SS)") (class "Default")
      (node (ref "C394") (pin "2") (pinfunction "2_2") (pintype "passive"))
      (node (ref "U45") (pin "6") (pinfunction "SS_6") (pintype "passive"))
    )
    (net (code "22") (name "Net-(U46-AVIN)") (class "Default")
      (node (ref "C408") (pin "1") (pinfunction "1_1") (pintype "passive"))
      (node (ref "R286") (pin "1") (pinfunction "1_1") (pintype "passive"))
      (node (ref "U46") (pin "47") (pinfunction "AVIN_47") (pintype "power_in"))
    )
    (net (code "23") (name "Net-(U46-BGND)") (class "Default")
      (node (ref "C411") (pin "2") (pinfunction "2_2") (pintype "passive"))
      (node (ref "U46") (pin "35") (pinfunction "BGND_35") (pintype "power_in"))
    )
    (net (code "24") (name "Net-(U46-BTMP)") (class "Default")
      (node (ref "C410") (pin "2") (pinfunction "2_2") (pintype "passive"))
      (node (ref "U46") (pin "33") (pinfunction "BTMP_33") (pintype "power_in"))
    )
    (net (code "25") (name "Net-(U46-PG)") (class "Default")
      (node (ref "C410") (pin "1") (pinfunction "1_1") (pintype "passive"))
      (node (ref "U46") (pin "32") (pinfunction "PG_32") (pintype "power_in"))
    )
    (net (code "26") (name "Net-(U46-SS)") (class "Default")
      (node (ref "C412") (pin "1") (pinfunction "1_1") (pintype "passive"))
      (node (ref "U46") (pin "43") (pinfunction "SS_43") (pintype "power_in"))
    )
    (net (code "27") (name "Net-(U46-SYNC)") (class "Default")
      (node (ref "R294") (pin "1") (pinfunction "1_1") (pintype "passive"))
      (node (ref "U46") (pin "36") (pinfunction "SYNC_36") (pintype "power_in"))
    )
    (net (code "28") (name "Net-(U46-VDDB)") (class "Default")
      (node (ref "C411") (pin "1") (pinfunction "1_1") (pintype "passive"))
      (node (ref "U46") (pin "34") (pinfunction "VDDB_34") (pintype "power_in"))
    )
    (net (code "29") (name "Net-(U46-VFB)") (class "Default")
      (node (ref "R287") (pin "1") (pinfunction "1_1") (pintype "passive"))
      (node (ref "R289") (pin "1") (pinfunction "1_1") (pintype "passive"))
      (node (ref "R291") (pin "2") (pinfunction "2_2") (pintype "passive"))
      (node (ref "U46") (pin "44") (pinfunction "VFB_44") (pintype "power_in"))
    )
    (net (code "30") (name "Net-(U47-FB)") (class "Default")
      (node (ref "R288") (pin "1") (pinfunction "1_1") (pintype "passive"))
      (node (ref "R290") (pin "2") (pinfunction "2_2") (pintype "passive"))
      (node (ref "U47") (pin "7") (pinfunction "FB_7") (pintype "passive"))
    )
    (net (code "31") (name "Net-(U47-SS)") (class "Default")
      (node (ref "C409") (pin "2") (pinfunction "2_2") (pintype "passive"))
      (node (ref "U47") (pin "6") (pinfunction "SS_6") (pintype "passive"))
    )
    (net (code "32") (name "Net-(U48-EN)") (class "Default")
      (node (ref "R296") (pin "1") (pinfunction "1_1") (pintype "passive"))
      (node (ref "R297") (pin "2") (pinfunction "2_2") (pintype "passive"))
      (node (ref "U48") (pin "5") (pinfunction "EN_5") (pintype "passive"))
    )
    (net (code "33") (name "Net-(U48-FB)") (class "Default")
      (node (ref "R295") (pin "1") (pinfunction "1_1") (pintype "passive"))
      (node (ref "R298") (pin "2") (pinfunction "2_2") (pintype "passive"))
      (node (ref "U48") (pin "7") (pinfunction "FB_7") (pintype "passive"))
    )
    (net (code "34") (name "Net-(U48-SS)") (class "Default")
      (node (ref "C415") (pin "2") (pinfunction "2_2") (pintype "passive"))
      (node (ref "U48") (pin "6") (pinfunction "SS_6") (pintype "passive"))
    )
    (net (code "35") (name "PVIN_5V") (class "Default")
      (node (ref "C380") (pin "1") (pinfunction "1_1") (pintype "passive"))
      (node (ref "C381") (pin "2") (pinfunction "2_2") (pintype "passive"))
      (node (ref "C382") (pin "2") (pinfunction "2_2") (pintype "passive"))
      (node (ref "C383") (pin "2") (pinfunction "2_2") (pintype "passive"))
      (node (ref "C384") (pin "1") (pinfunction "1_1") (pintype "passive"))
      (node (ref "C385") (pin "1") (pinfunction "1_1") (pintype "passive"))
      (node (ref "C397") (pin "2") (pinfunction "2_2") (pintype "passive"))
      (node (ref "C444") (pin "2") (pinfunction "2_2") (pintype "passive"))
      (node (ref "C445") (pin "2") (pinfunction "2_2") (pintype "passive"))
      (node (ref "C80") (pin "1") (pinfunction "1_1") (pintype "passive"))
      (node (ref "FB34") (pin "1") (pinfunction "1_1") (pintype "passive"))
      (node (ref "FB35") (pin "1") (pinfunction "1_1") (pintype "passive"))
      (node (ref "P2") (pin "1") (pinfunction "1_1") (pintype "bidirectional"))
      (node (ref "U44") (pin "1") (pinfunction "PVIN_1") (pintype "power_in"))
      (node (ref "U44") (pin "11") (pinfunction "PVIN_11") (pintype "power_in"))
      (node (ref "U44") (pin "12") (pinfunction "PVIN_12") (pintype "power_in"))
      (node (ref "U44") (pin "3") (pinfunction "VIN_3") (pintype "power_in"))
      (node (ref "U44") (pin "39") (pinfunction "PVIN_39") (pintype "power_in"))
      (node (ref "U44") (pin "40") (pinfunction "PVIN_40") (pintype "power_in"))
    )
    (net (code "36") (name "unconnected-(U44-DNC-Pad5)") (class "Default")
      (node (ref "U44") (pin "5") (pinfunction "DNC_5") (pintype "power_in+no_connect"))
    )
    (net (code "37") (name "unconnected-(U44-DNC-Pad9)") (class "Default")
      (node (ref "U44") (pin "9") (pinfunction "DNC_9") (pintype "power_in+no_connect"))
    )
    (net (code "38") (name "unconnected-(U44-DNC-Pad24)") (class "Default")
      (node (ref "U44") (pin "24") (pinfunction "DNC_24") (pintype "power_in+no_connect"))
    )
    (net (code "39") (name "unconnected-(U44-ILIM-Pad6)") (class "Default")
      (node (ref "U44") (pin "6") (pinfunction "ILIM_6") (pintype "power_in+no_connect"))
    )
    (net (code "40") (name "unconnected-(U44-INH{slash}UVLO-Pad30)") (class "Default")
      (node (ref "U44") (pin "30") (pinfunction "INH/UVLO_30") (pintype "power_in+no_connect"))
    )
    (net (code "41") (name "unconnected-(U44-ISHARE-Pad25)") (class "Default")
      (node (ref "U44") (pin "25") (pinfunction "ISHARE_25") (pintype "power_in+no_connect"))
    )
    (net (code "42") (name "unconnected-(U44-OCP_SEL-Pad4)") (class "Default")
      (node (ref "U44") (pin "4") (pinfunction "OCP_SEL_4") (pintype "power_in+no_connect"))
    )
    (net (code "43") (name "unconnected-(U44-SYNC_OUT-Pad7)") (class "Default")
      (node (ref "U44") (pin "7") (pinfunction "SYNC_OUT_7") (pintype "power_in+no_connect"))
    )
    (net (code "44") (name "unconnected-(U46-EAOUT-Pad41)") (class "Default")
      (node (ref "U46") (pin "41") (pinfunction "EAOUT_41") (pintype "power_in+no_connect"))
    )
    (net (code "45") (name "unconnected-(U46-NC(SW)-Pad19)") (class "Default")
      (node (ref "U46") (pin "19") (pinfunction "NC(SW)_19") (pintype "power_in+no_connect"))
    )
    (net (code "46") (name "unconnected-(U46-NC(SW)-Pad20)") (class "Default")
      (node (ref "U46") (pin "20") (pinfunction "NC(SW)_20") (pintype "power_in+no_connect"))
    )
    (net (code "47") (name "unconnected-(U46-NC(SW)-Pad49)") (class "Default")
      (node (ref "U46") (pin "49") (pinfunction "NC(SW)_49") (pintype "power_in+no_connect"))
    )
    (net (code "48") (name "unconnected-(U46-NC(SW)-Pad50)") (class "Default")
      (node (ref "U46") (pin "50") (pinfunction "NC(SW)_50") (pintype "power_in+no_connect"))
    )
    (net (code "49") (name "unconnected-(U46-NC(SW)-Pad51)") (class "Default")
      (node (ref "U46") (pin "51") (pinfunction "NC(SW)_51") (pintype "power_in+no_connect"))
    )
    (net (code "50") (name "unconnected-(U46-NC(SW)-Pad52)") (class "Default")
      (node (ref "U46") (pin "52") (pinfunction "NC(SW)_52") (pintype "power_in+no_connect"))
    )
    (net (code "51") (name "unconnected-(U46-NC-Pad1)") (class "Default")
      (node (ref "U46") (pin "1") (pinfunction "NC_1") (pintype "power_in+no_connect"))
    )
    (net (code "52") (name "unconnected-(U46-NC-Pad2)") (class "Default")
      (node (ref "U46") (pin "2") (pinfunction "NC_2") (pintype "power_in+no_connect"))
    )
    (net (code "53") (name "unconnected-(U46-NC-Pad3)") (class "Default")
      (node (ref "U46") (pin "3") (pinfunction "NC_3") (pintype "power_in+no_connect"))
    )
    (net (code "54") (name "unconnected-(U46-NC-Pad4)") (class "Default")
      (node (ref "U46") (pin "4") (pinfunction "NC_4") (pintype "power_in+no_connect"))
    )
    (net (code "55") (name "unconnected-(U46-NC-Pad5)") (class "Default")
      (node (ref "U46") (pin "5") (pinfunction "NC_5") (pintype "power_in+no_connect"))
    )
    (net (code "56") (name "unconnected-(U46-NC-Pad6)") (class "Default")
      (node (ref "U46") (pin "6") (pinfunction "NC_6") (pintype "power_in+no_connect"))
    )
    (net (code "57") (name "unconnected-(U46-NC-Pad7)") (class "Default")
      (node (ref "U46") (pin "7") (pinfunction "NC_7") (pintype "power_in+no_connect"))
    )
    (net (code "58") (name "unconnected-(U46-NC-Pad8)") (class "Default")
      (node (ref "U46") (pin "8") (pinfunction "NC_8") (pintype "power_in+no_connect"))
    )
    (net (code "59") (name "unconnected-(U46-NC-Pad9)") (class "Default")
      (node (ref "U46") (pin "9") (pinfunction "NC_9") (pintype "power_in+no_connect"))
    )
    (net (code "60") (name "unconnected-(U46-NC-Pad18)") (class "Default")
      (node (ref "U46") (pin "18") (pinfunction "NC_18") (pintype "power_in+no_connect"))
    )
    (net (code "61") (name "unconnected-(U46-NC-Pad37)") (class "Default")
      (node (ref "U46") (pin "37") (pinfunction "NC_37") (pintype "power_in+no_connect"))
    )
    (net (code "62") (name "unconnected-(U46-NC-Pad40)") (class "Default")
      (node (ref "U46") (pin "40") (pinfunction "NC_40") (pintype "power_in+no_connect"))
    )
    (net (code "63") (name "unconnected-(U46-NC-Pad42)") (class "Default")
      (node (ref "U46") (pin "42") (pinfunction "NC_42") (pintype "power_in+no_connect"))
    )
    (net (code "64") (name "unconnected-(U46-NC-Pad45)") (class "Default")
      (node (ref "U46") (pin "45") (pinfunction "NC_45") (pintype "power_in+no_connect"))
    )
    (net (code "65") (name "unconnected-(U46-NC-Pad48)") (class "Default")
      (node (ref "U46") (pin "48") (pinfunction "NC_48") (pintype "power_in+no_connect"))
    )
    (net (code "66") (name "unconnected-(U46-NC-Pad53)") (class "Default")
      (node (ref "U46") (pin "53") (pinfunction "NC_53") (pintype "power_in+no_connect"))
    )
    (net (code "67") (name "unconnected-(U46-NC-Pad54)") (class "Default")
      (node (ref "U46") (pin "54") (pinfunction "NC_54") (pintype "power_in+no_connect"))
    )
  )
)
